# Tone_Control.net
KiCad netlist of a schematic drawn in EAGLE
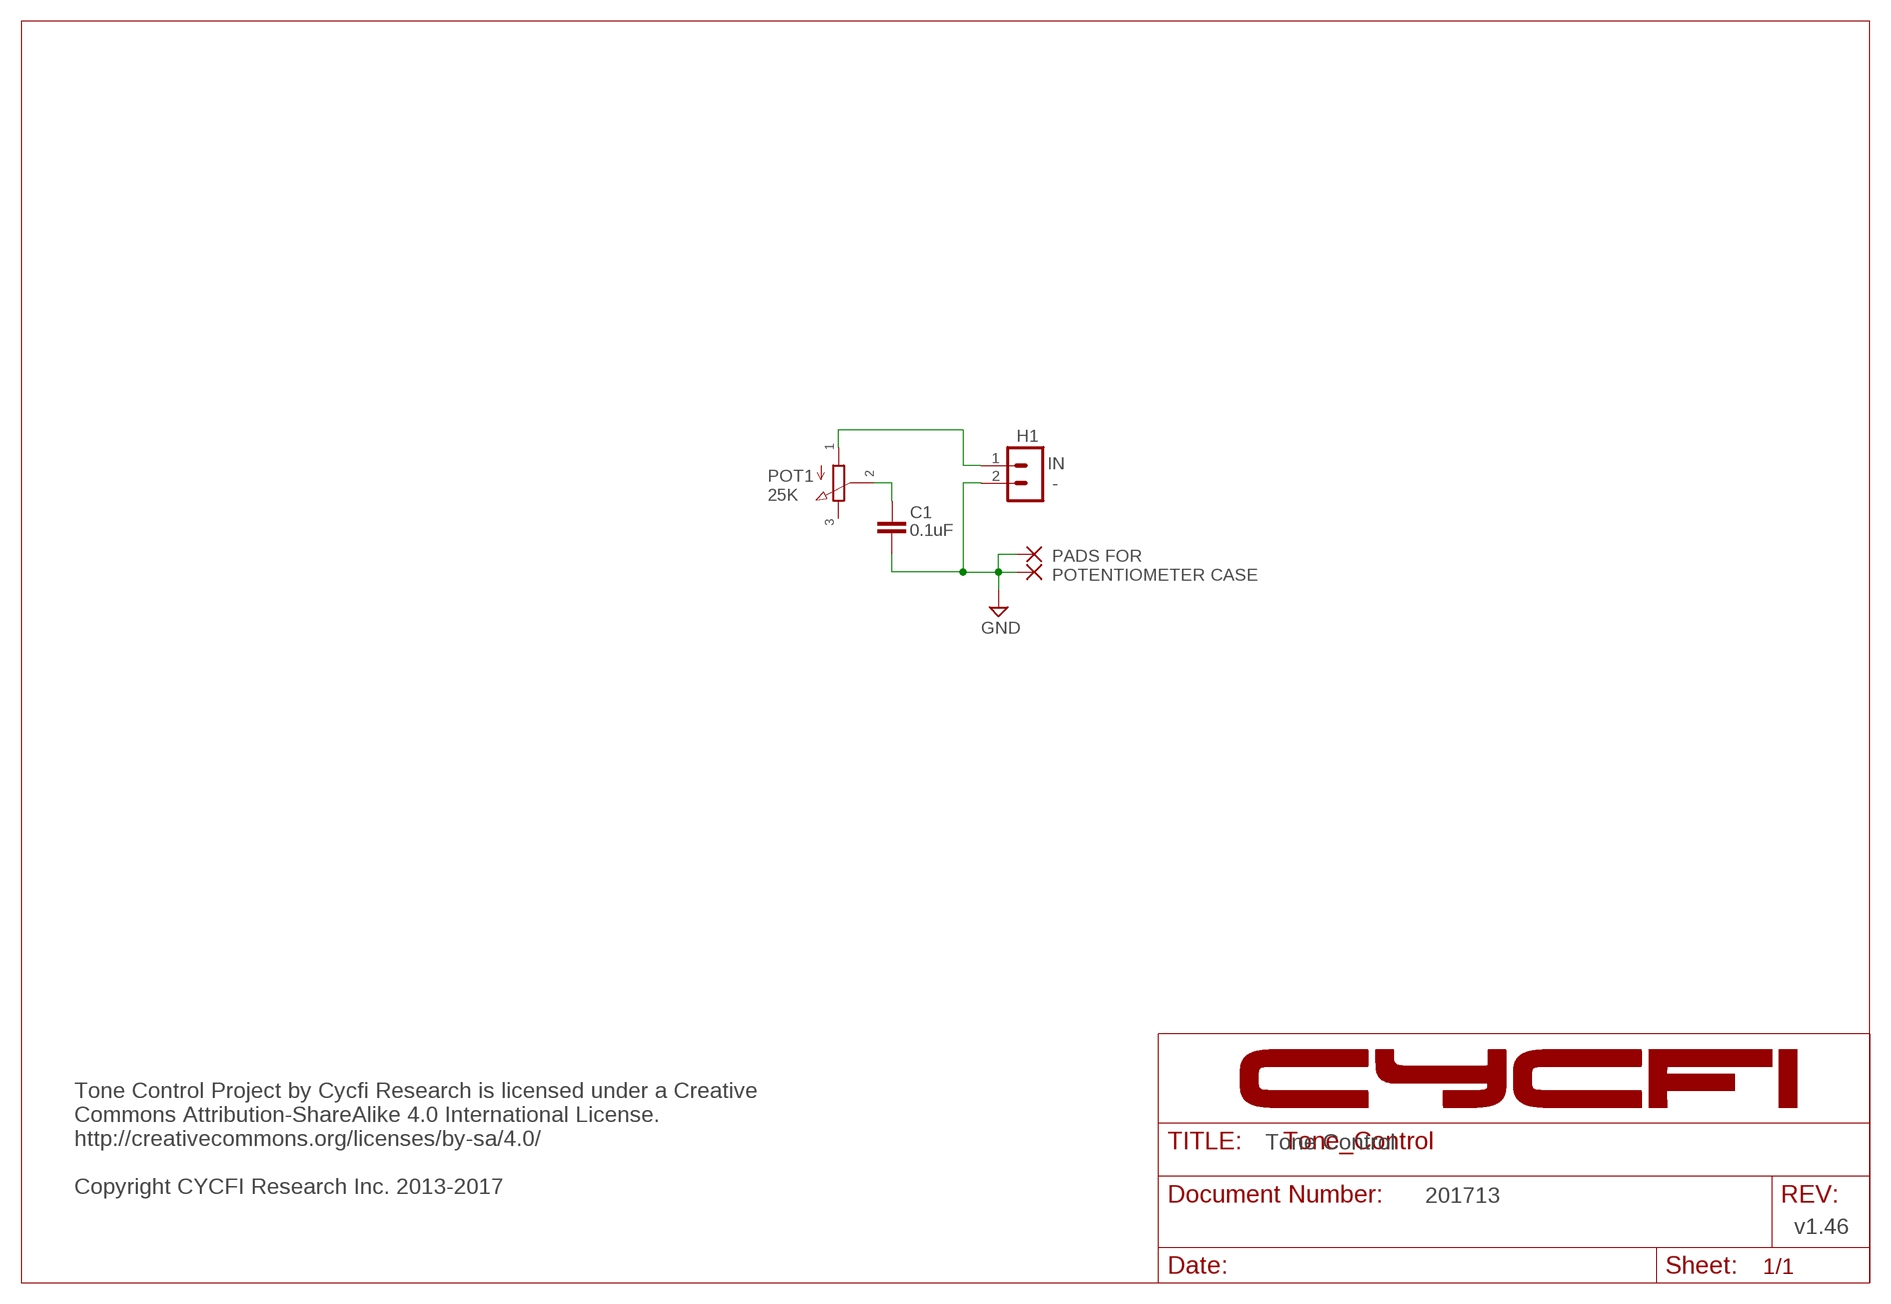
[diagram p0: schematic, sheet 1]

(export (version "E")
  (design (tool "Eeschema 10.0.6"))
  (components
    (comp (ref "C1")
      (value "0.1uF")
      (footprint "eagle-import:C0603")
      (libsource (lib "eagle-import") (part "C-EUC0603"))
    )
    (comp (ref "GND3")
      (value "SMD2")
      (footprint "eagle-import:SMD1,27-2,54")
      (libsource (lib "eagle-import") (part "SMD2"))
    )
    (comp (ref "GND4")
      (value "SMD2")
      (footprint "eagle-import:SMD1,27-2,54")
      (libsource (lib "eagle-import") (part "SMD2"))
    )
    (comp (ref "H1")
      (value "MA02-1")
      (footprint "eagle-import:MA02-1")
      (libsource (lib "eagle-import") (part "MA02-1"))
    )
    (comp (ref "POT1")
      (value "PDB181-GTR01")
      (footprint "eagle-import:PDB181")
      (libsource (lib "eagle-import") (part "PDB181-GTR01"))
    )
  )
  (nets
    (net (code "1") (name "GND") (class "Default")
      (node (ref "C1") (pin "1") (pinfunction "1_1") (pintype "passive"))
      (node (ref "GND3") (pin "1") (pinfunction "P_1") (pintype "passive"))
      (node (ref "GND4") (pin "1") (pinfunction "P_1") (pintype "passive"))
      (node (ref "H1") (pin "2") (pinfunction "2_2") (pintype "passive"))
    )
    (net (code "2") (name "Net-(POT1-1)") (class "Default")
      (node (ref "H1") (pin "1") (pinfunction "1_1") (pintype "passive"))
      (node (ref "POT1") (pin "P$1") (pinfunction "1_P$1") (pintype "passive"))
    )
    (net (code "3") (name "Net-(POT1-2)") (class "Default")
      (node (ref "C1") (pin "2") (pinfunction "2_2") (pintype "passive"))
      (node (ref "POT1") (pin "P$2") (pinfunction "2_P$2") (pintype "passive"))
    )
    (net (code "4") (name "unconnected-(POT1-3-PadP$3)") (class "Default")
      (node (ref "POT1") (pin "P$3") (pinfunction "3_P$3") (pintype "passive"))
    )
  )
)
